# Wattuino-Nanite841_v10.net
KiCad netlist of a schematic drawn in EAGLE
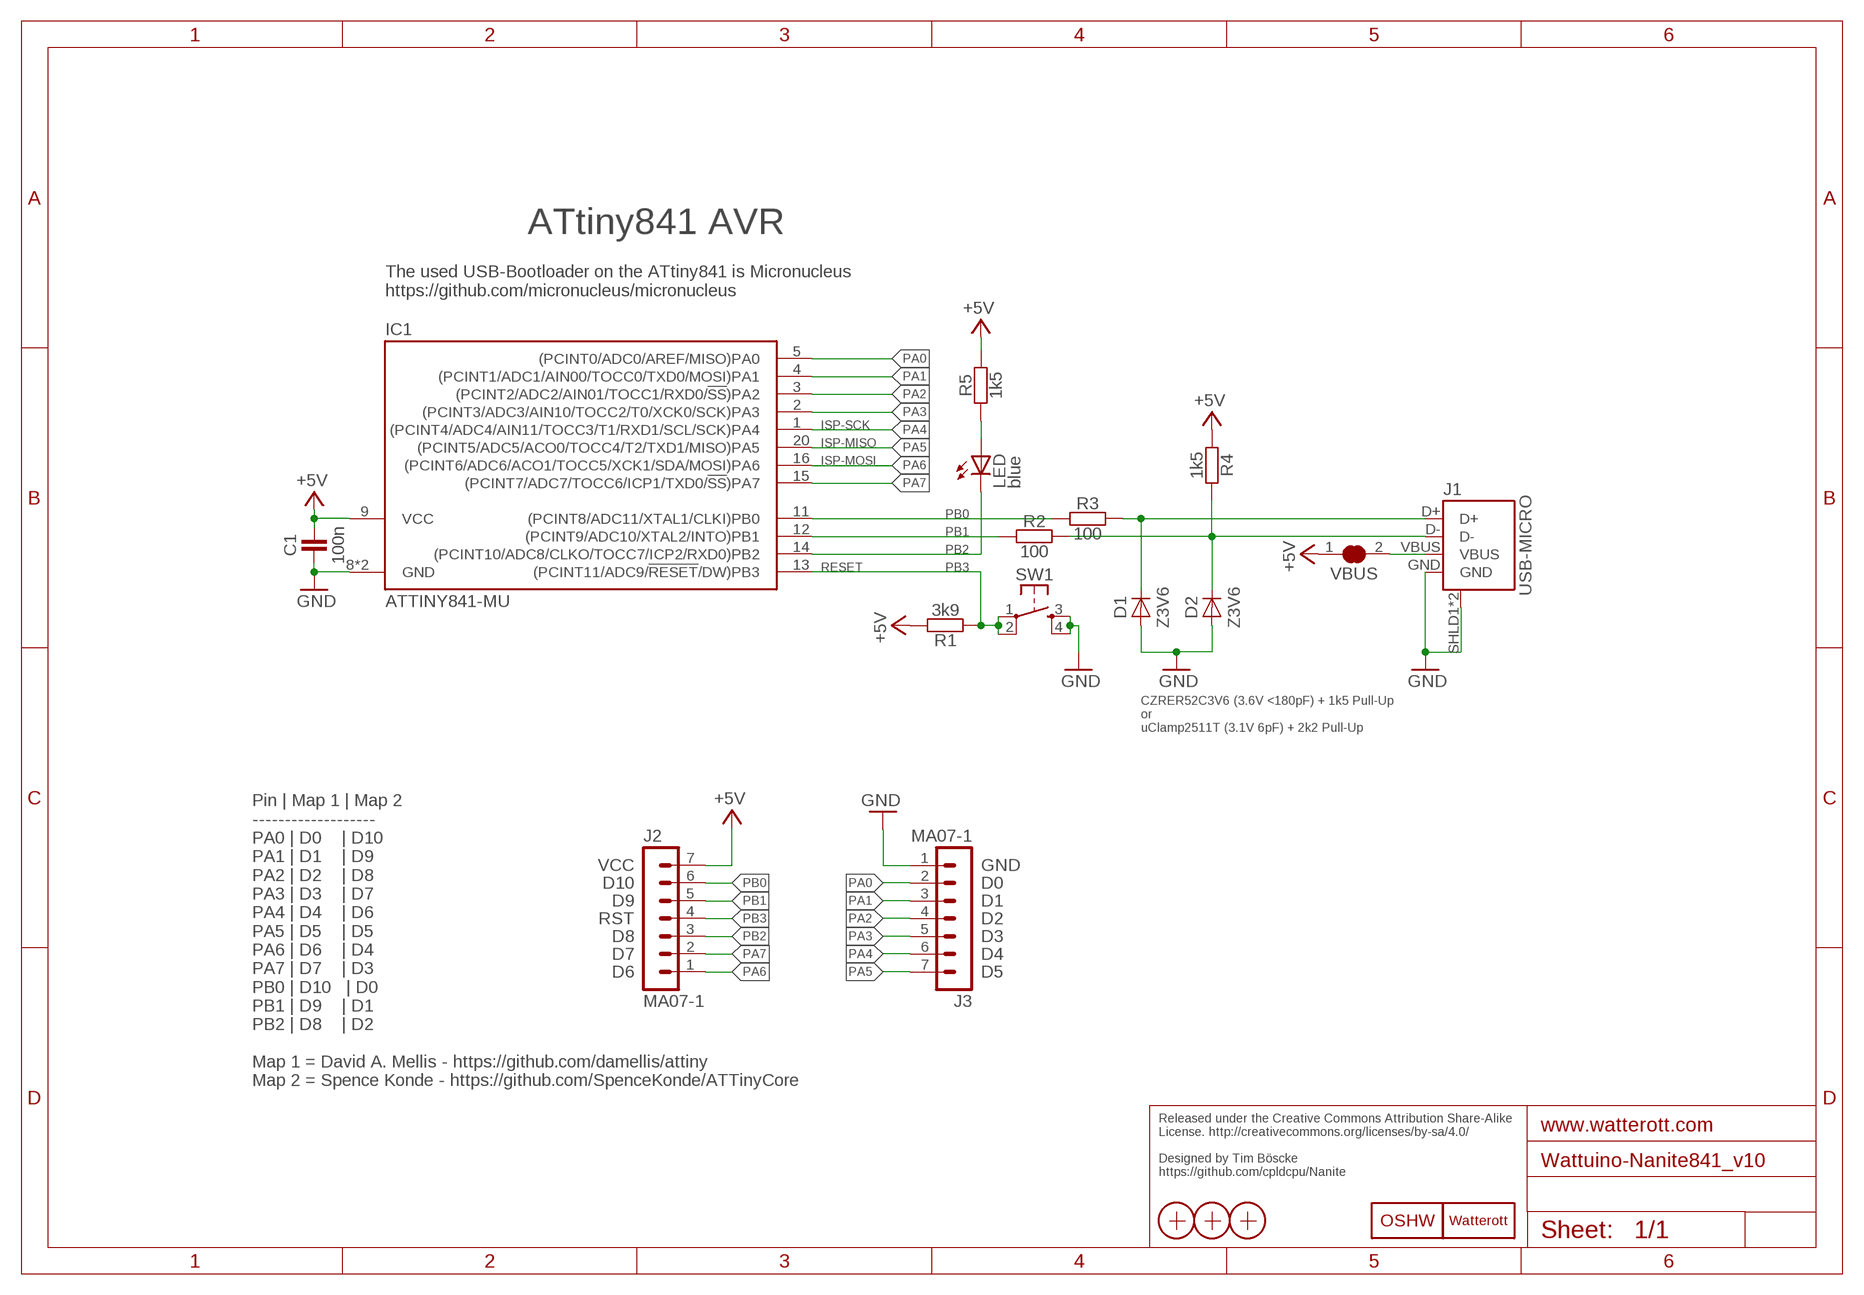
[diagram p0: schematic, sheet 1]

(export (version "E")
  (design (tool "Eeschema 10.0.6"))
  (components
    (comp (ref "C1")
      (value "100n")
      (footprint "eagle-import:C0402")
      (libsource (lib "eagle-import") (part "CAPACITOR-0402"))
    )
    (comp (ref "D1")
      (value "Z3V6")
      (footprint "eagle-import:SOD882")
      (libsource (lib "eagle-import") (part "DIODE-SOD882"))
    )
    (comp (ref "D2")
      (value "Z3V6")
      (footprint "eagle-import:SOD882")
      (libsource (lib "eagle-import") (part "DIODE-SOD882"))
    )
    (comp (ref "IC1")
      (value "ATTINY841-MU")
      (footprint "eagle-import:QFN20-PAD")
      (libsource (lib "eagle-import") (part "ATTINY841-MU"))
    )
    (comp (ref "J1")
      (value "USB-MICRO")
      (footprint "eagle-import:USB-MICRO-10103594")
      (libsource (lib "eagle-import") (part "USB-MICRO"))
    )
    (comp (ref "J2")
      (value "MA07-1")
      (footprint "eagle-import:MA07-1")
      (libsource (lib "eagle-import") (part "MA07-1"))
    )
    (comp (ref "J3")
      (value "MA07-1")
      (footprint "eagle-import:MA07-1")
      (libsource (lib "eagle-import") (part "MA07-1"))
    )
    (comp (ref "LED")
      (value "blue")
      (footprint "eagle-import:C0603")
      (libsource (lib "eagle-import") (part "LED-0603"))
    )
    (comp (ref "LOGO1")
      (value "LOGO-S_PLACE_S")
      (footprint "eagle-import:SPARK_TPLACE_S")
      (libsource (lib "eagle-import") (part "LOGO-S_PLACE_S"))
    )
    (comp (ref "LOGO2")
      (value "OSHW_LOGOX0070")
      (footprint "eagle-import:OSHW_6X70")
      (libsource (lib "eagle-import") (part "OSHW_LOGOX0070"))
    )
    (comp (ref "R1")
      (value "3k9")
      (footprint "eagle-import:C0402")
      (libsource (lib "eagle-import") (part "RESISTOR-0402"))
    )
    (comp (ref "R2")
      (value "100")
      (footprint "eagle-import:C0402")
      (libsource (lib "eagle-import") (part "RESISTOR-0402"))
    )
    (comp (ref "R3")
      (value "100")
      (footprint "eagle-import:C0402")
      (libsource (lib "eagle-import") (part "RESISTOR-0402"))
    )
    (comp (ref "R4")
      (value "1k5")
      (footprint "eagle-import:C0402")
      (libsource (lib "eagle-import") (part "RESISTOR-0402"))
    )
    (comp (ref "R5")
      (value "1k5")
      (footprint "eagle-import:C0402")
      (libsource (lib "eagle-import") (part "RESISTOR-0402"))
    )
    (comp (ref "SW1")
      (value "SW-TACTILE-PTS840P")
      (footprint "eagle-import:SW_PTS840P")
      (libsource (lib "eagle-import") (part "SW-TACTILE-PTS840P"))
    )
    (comp (ref "VBUS")
      (value "JUMPER2-0603-NC")
      (footprint "eagle-import:JUMPER2-0603_NC")
      (libsource (lib "eagle-import") (part "JUMPER2-0603-NC"))
    )
    (comp (ref "X1")
      (value "PASSER-07")
      (footprint "eagle-import:PASSER_07MM")
      (libsource (lib "eagle-import") (part "PASSER-07"))
    )
    (comp (ref "X2")
      (value "PASSER-07")
      (footprint "eagle-import:PASSER_07MM")
      (libsource (lib "eagle-import") (part "PASSER-07"))
    )
    (comp (ref "X3")
      (value "PASSER-07")
      (footprint "eagle-import:PASSER_07MM")
      (libsource (lib "eagle-import") (part "PASSER-07"))
    )
  )
  (nets
    (net (code "1") (name "+5V") (class "Default")
      (node (ref "C1") (pin "2") (pinfunction "2_2") (pintype "passive"))
      (node (ref "IC1") (pin "9") (pinfunction "VCC_9") (pintype "power_in"))
      (node (ref "J2") (pin "7") (pinfunction "7_7") (pintype "passive"))
      (node (ref "R1") (pin "2") (pinfunction "2_2") (pintype "passive"))
      (node (ref "R4") (pin "1") (pinfunction "1_1") (pintype "passive"))
      (node (ref "R5") (pin "2") (pinfunction "2_2") (pintype "passive"))
      (node (ref "VBUS") (pin "1") (pinfunction "1_1") (pintype "passive"))
    )
    (net (code "2") (name "GND") (class "Default")
      (node (ref "C1") (pin "1") (pinfunction "1_1") (pintype "passive"))
      (node (ref "D1") (pin "A") (pinfunction "A_A") (pintype "passive"))
      (node (ref "D2") (pin "A") (pinfunction "A_A") (pintype "passive"))
      (node (ref "IC1") (pin "8") (pinfunction "GND_8") (pintype "power_in"))
      (node (ref "IC1") (pin "TP") (pinfunction "GND_TP") (pintype "power_in"))
      (node (ref "J1") (pin "GND") (pinfunction "GND_GND") (pintype "power_in"))
      (node (ref "J1") (pin "SHLD1") (pinfunction "SHIELD_SHLD1") (pintype "passive"))
      (node (ref "J1") (pin "SHLD2") (pinfunction "SHIELD_SHLD2") (pintype "passive"))
      (node (ref "J3") (pin "1") (pinfunction "1_1") (pintype "passive"))
      (node (ref "SW1") (pin "3") (pinfunction "S1_3") (pintype "passive"))
      (node (ref "SW1") (pin "4") (pinfunction "S2_4") (pintype "passive"))
    )
    (net (code "3") (name "Net-(D1-PadC)") (class "Default")
      (node (ref "D1") (pin "C") (pinfunction "C_C") (pintype "passive"))
      (node (ref "J1") (pin "D+") (pinfunction "D+_D+") (pintype "bidirectional"))
      (node (ref "R3") (pin "2") (pinfunction "2_2") (pintype "passive"))
    )
    (net (code "4") (name "Net-(D2-PadC)") (class "Default")
      (node (ref "D2") (pin "C") (pinfunction "C_C") (pintype "passive"))
      (node (ref "J1") (pin "D-") (pinfunction "D-_D-") (pintype "bidirectional"))
      (node (ref "R2") (pin "2") (pinfunction "2_2") (pintype "passive"))
      (node (ref "R4") (pin "2") (pinfunction "2_2") (pintype "passive"))
    )
    (net (code "5") (name "Net-(J1-PadVBUS)") (class "Default")
      (node (ref "J1") (pin "VBUS") (pinfunction "VBUS_VBUS") (pintype "power_in"))
      (node (ref "VBUS") (pin "2") (pinfunction "2_2") (pintype "passive"))
    )
    (net (code "6") (name "Net-(LED-PadA)") (class "Default")
      (node (ref "LED") (pin "A") (pinfunction "A_A") (pintype "passive"))
      (node (ref "R5") (pin "1") (pinfunction "1_1") (pintype "passive"))
    )
    (net (code "7") (name "PA0") (class "Default")
      (node (ref "IC1") (pin "5") (pinfunction "(PCINT0/ADC0/AREF/MISO)PA0_5") (pintype "bidirectional"))
      (node (ref "J3") (pin "2") (pinfunction "2_2") (pintype "passive"))
    )
    (net (code "8") (name "PA1") (class "Default")
      (node (ref "IC1") (pin "4") (pinfunction "(PCINT1/ADC1/AIN00/TOCC0/TXD0/MOSI)PA1_4") (pintype "bidirectional"))
      (node (ref "J3") (pin "3") (pinfunction "3_3") (pintype "passive"))
    )
    (net (code "9") (name "PA2") (class "Default")
      (node (ref "IC1") (pin "3") (pinfunction "(PCINT2/ADC2/AIN01/TOCC1/RXD0/~{SS})PA2_3") (pintype "bidirectional"))
      (node (ref "J3") (pin "4") (pinfunction "4_4") (pintype "passive"))
    )
    (net (code "10") (name "PA3") (class "Default")
      (node (ref "IC1") (pin "2") (pinfunction "(PCINT3/ADC3/AIN10/TOCC2/T0/XCK0/SCK)PA3_2") (pintype "bidirectional"))
      (node (ref "J3") (pin "5") (pinfunction "5_5") (pintype "passive"))
    )
    (net (code "11") (name "PA4") (class "Default")
      (node (ref "IC1") (pin "1") (pinfunction "(PCINT4/ADC4/AIN11/TOCC3/T1/RXD1/SCL/SCK)PA4_1") (pintype "bidirectional"))
      (node (ref "J3") (pin "6") (pinfunction "6_6") (pintype "passive"))
    )
    (net (code "12") (name "PA5") (class "Default")
      (node (ref "IC1") (pin "20") (pinfunction "(PCINT5/ADC5/ACO0/TOCC4/T2/TXD1/MISO)PA5_20") (pintype "bidirectional"))
      (node (ref "J3") (pin "7") (pinfunction "7_7") (pintype "passive"))
    )
    (net (code "13") (name "PA6") (class "Default")
      (node (ref "IC1") (pin "16") (pinfunction "(PCINT6/ADC6/ACO1/TOCC5/XCK1/SDA/MOSI)PA6_16") (pintype "bidirectional"))
      (node (ref "J2") (pin "1") (pinfunction "1_1") (pintype "passive"))
    )
    (net (code "14") (name "PA7") (class "Default")
      (node (ref "IC1") (pin "15") (pinfunction "(PCINT7/ADC7/TOCC6/ICP1/TXD0/~{SS})PA7_15") (pintype "bidirectional"))
      (node (ref "J2") (pin "2") (pinfunction "2_2") (pintype "passive"))
    )
    (net (code "15") (name "PB0") (class "Default")
      (node (ref "IC1") (pin "11") (pinfunction "(PCINT8/ADC11/XTAL1/CLKI)PB0_11") (pintype "bidirectional"))
      (node (ref "J2") (pin "6") (pinfunction "6_6") (pintype "passive"))
      (node (ref "R3") (pin "1") (pinfunction "1_1") (pintype "passive"))
    )
    (net (code "16") (name "PB1") (class "Default")
      (node (ref "IC1") (pin "12") (pinfunction "(PCINT9/ADC10/XTAL2/INTO)PB1_12") (pintype "bidirectional"))
      (node (ref "J2") (pin "5") (pinfunction "5_5") (pintype "passive"))
      (node (ref "R2") (pin "1") (pinfunction "1_1") (pintype "passive"))
    )
    (net (code "17") (name "PB2") (class "Default")
      (node (ref "IC1") (pin "14") (pinfunction "(PCINT10/ADC8/CLKO/TOCC7/ICP2/RXD0)PB2_14") (pintype "bidirectional"))
      (node (ref "J2") (pin "3") (pinfunction "3_3") (pintype "passive"))
      (node (ref "LED") (pin "C") (pinfunction "C_C") (pintype "passive"))
    )
    (net (code "18") (name "PB3") (class "Default")
      (node (ref "IC1") (pin "13") (pinfunction "(PCINT11/ADC9/~{RESET}/DW)PB3_13") (pintype "bidirectional"))
      (node (ref "J2") (pin "4") (pinfunction "4_4") (pintype "passive"))
      (node (ref "R1") (pin "1") (pinfunction "1_1") (pintype "passive"))
      (node (ref "SW1") (pin "1") (pinfunction "P1_1") (pintype "passive"))
      (node (ref "SW1") (pin "2") (pinfunction "P2_2") (pintype "passive"))
    )
  )
)
